# InterfacesA_FPGA.net
KiCad netlist of a schematic drawn in Altium Designer
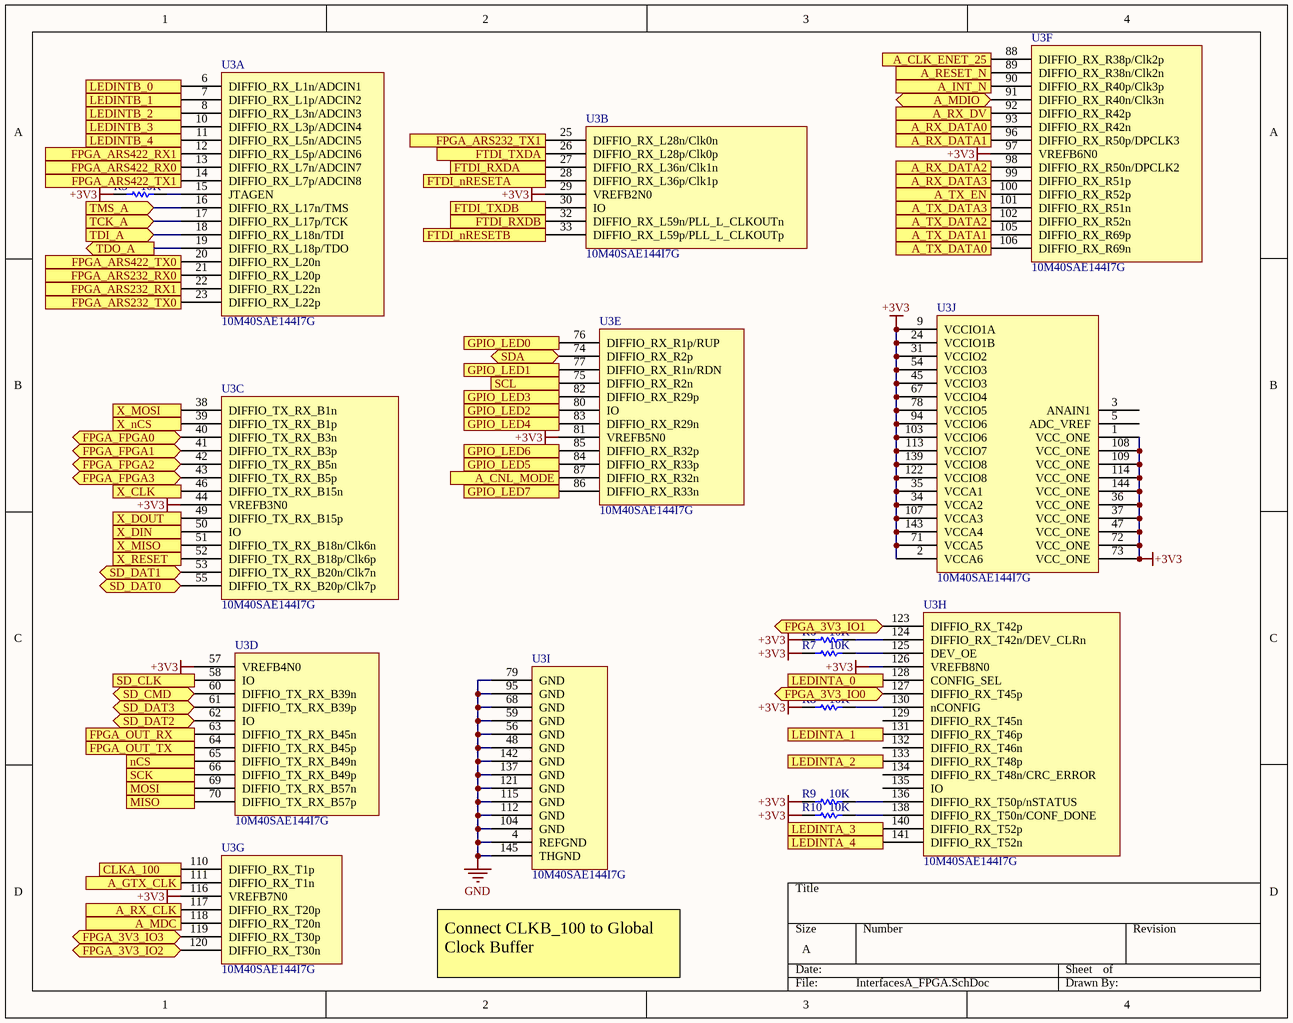
[diagram p0: InterfacesA_FPGA.SchDoc]

(export (version "E")
  (design (tool "Eeschema 10.0.6"))
  (components
    (comp (ref "R5")
      (value "10K")
      (footprint "RES_0805")
      (fields (field (name "Comment") "RES_0805"))
      (libsource (lib "AdapterLib") (part "RES_0805"))
    )
    (comp (ref "R6")
      (value "10K")
      (footprint "RES_0805")
      (fields (field (name "Comment") "RES_0805"))
      (libsource (lib "AdapterLib") (part "RES_0805"))
    )
    (comp (ref "R7")
      (value "10K")
      (footprint "RES_0805")
      (fields (field (name "Comment") "RES_0805"))
      (libsource (lib "AdapterLib") (part "RES_0805"))
    )
    (comp (ref "R8")
      (value "10K")
      (footprint "RES_0805")
      (fields (field (name "Comment") "RES_0805"))
      (libsource (lib "AdapterLib") (part "RES_0805"))
    )
    (comp (ref "R9")
      (value "10K")
      (footprint "RES_0805")
      (fields (field (name "Comment") "RES_0805"))
      (libsource (lib "AdapterLib") (part "RES_0805"))
    )
    (comp (ref "R10")
      (value "10K")
      (footprint "RES_0805")
      (fields (field (name "Comment") "RES_0805"))
      (libsource (lib "AdapterLib") (part "RES_0805"))
    )
    (comp (ref "U3")
      (value "10M40SAE144I7G")
      (footprint "10M40SAE144I7G")
      (description "IC FPGA 101 I/O 144EQFP")
      (libsource (lib "AdapterLib") (part "10M40SAE144I7G"))
    )
  )
  (nets
    (net (code "1") (name "+3V3") (class "Default")
      (node (ref "R10") (pin "2") (pinfunction "2_2") (pintype "passive"))
      (node (ref "R5") (pin "2") (pinfunction "2_2") (pintype "passive"))
      (node (ref "R6") (pin "2") (pinfunction "2_2") (pintype "passive"))
      (node (ref "R7") (pin "2") (pinfunction "2_2") (pintype "passive"))
      (node (ref "R8") (pin "2") (pinfunction "2_2") (pintype "passive"))
      (node (ref "R9") (pin "2") (pinfunction "2_2") (pintype "passive"))
      (node (ref "U3") (pin "1") (pinfunction "VCC_ONE_1") (pintype "passive"))
      (node (ref "U3") (pin "103") (pinfunction "VCCIO6_103") (pintype "passive"))
      (node (ref "U3") (pin "107") (pinfunction "VCCA3_107") (pintype "passive"))
      (node (ref "U3") (pin "108") (pinfunction "VCC_ONE_108") (pintype "passive"))
      (node (ref "U3") (pin "109") (pinfunction "VCC_ONE_109") (pintype "passive"))
      (node (ref "U3") (pin "113") (pinfunction "VCCIO7_113") (pintype "passive"))
      (node (ref "U3") (pin "114") (pinfunction "VCC_ONE_114") (pintype "passive"))
      (node (ref "U3") (pin "116") (pinfunction "VREFB7N0_116") (pintype "passive"))
      (node (ref "U3") (pin "122") (pinfunction "VCCIO8_122") (pintype "passive"))
      (node (ref "U3") (pin "126") (pinfunction "VREFB8N0_126") (pintype "passive"))
      (node (ref "U3") (pin "139") (pinfunction "VCCIO8_139") (pintype "passive"))
      (node (ref "U3") (pin "143") (pinfunction "VCCA4_143") (pintype "passive"))
      (node (ref "U3") (pin "144") (pinfunction "VCC_ONE_144") (pintype "passive"))
      (node (ref "U3") (pin "2") (pinfunction "VCCA6_2") (pintype "passive"))
      (node (ref "U3") (pin "24") (pinfunction "VCCIO1B_24") (pintype "passive"))
      (node (ref "U3") (pin "29") (pinfunction "VREFB2N0_29") (pintype "passive"))
      (node (ref "U3") (pin "31") (pinfunction "VCCIO2_31") (pintype "passive"))
      (node (ref "U3") (pin "34") (pinfunction "VCCA2_34") (pintype "passive"))
      (node (ref "U3") (pin "35") (pinfunction "VCCA1_35") (pintype "passive"))
      (node (ref "U3") (pin "36") (pinfunction "VCC_ONE_36") (pintype "passive"))
      (node (ref "U3") (pin "37") (pinfunction "VCC_ONE_37") (pintype "passive"))
      (node (ref "U3") (pin "44") (pinfunction "VREFB3N0_44") (pintype "passive"))
      (node (ref "U3") (pin "45") (pinfunction "VCCIO3_45") (pintype "passive"))
      (node (ref "U3") (pin "47") (pinfunction "VCC_ONE_47") (pintype "passive"))
      (node (ref "U3") (pin "54") (pinfunction "VCCIO3_54") (pintype "passive"))
      (node (ref "U3") (pin "57") (pinfunction "VREFB4N0_57") (pintype "passive"))
      (node (ref "U3") (pin "67") (pinfunction "VCCIO4_67") (pintype "passive"))
      (node (ref "U3") (pin "71") (pinfunction "VCCA5_71") (pintype "passive"))
      (node (ref "U3") (pin "72") (pinfunction "VCC_ONE_72") (pintype "passive"))
      (node (ref "U3") (pin "73") (pinfunction "VCC_ONE_73") (pintype "passive"))
      (node (ref "U3") (pin "78") (pinfunction "VCCIO5_78") (pintype "passive"))
      (node (ref "U3") (pin "81") (pinfunction "VREFB5N0_81") (pintype "passive"))
      (node (ref "U3") (pin "9") (pinfunction "VCCIO1A_9") (pintype "passive"))
      (node (ref "U3") (pin "94") (pinfunction "VCCIO6_94") (pintype "passive"))
      (node (ref "U3") (pin "97") (pinfunction "VREFB6N0_97") (pintype "passive"))
    )
    (net (code "2") (name "/A_CLK_ENET_25") (class "Default")
      (node (ref "U3") (pin "88") (pinfunction "DIFFIO_RX_R38p/Clk2p_88") (pintype "passive"))
    )
    (net (code "3") (name "/A_CNL_MODE") (class "Default")
      (node (ref "U3") (pin "87") (pinfunction "DIFFIO_RX_R32n_87") (pintype "passive"))
    )
    (net (code "4") (name "/A_GTX_CLK") (class "Default")
      (node (ref "U3") (pin "111") (pinfunction "DIFFIO_RX_T1n_111") (pintype "passive"))
    )
    (net (code "5") (name "/A_INT_N") (class "Default")
      (node (ref "U3") (pin "90") (pinfunction "DIFFIO_RX_R40p/Clk3p_90") (pintype "passive"))
    )
    (net (code "6") (name "/A_MDC") (class "Default")
      (node (ref "U3") (pin "118") (pinfunction "DIFFIO_RX_T20n_118") (pintype "passive"))
    )
    (net (code "7") (name "/A_MDIO") (class "Default")
      (node (ref "U3") (pin "91") (pinfunction "DIFFIO_RX_R40n/Clk3n_91") (pintype "passive"))
    )
    (net (code "8") (name "/A_RESET_N") (class "Default")
      (node (ref "U3") (pin "89") (pinfunction "DIFFIO_RX_R38n/Clk2n_89") (pintype "passive"))
    )
    (net (code "9") (name "/A_RX_CLK") (class "Default")
      (node (ref "U3") (pin "117") (pinfunction "DIFFIO_RX_T20p_117") (pintype "passive"))
    )
    (net (code "10") (name "/A_RX_DATA0") (class "Default")
      (node (ref "U3") (pin "93") (pinfunction "DIFFIO_RX_R42n_93") (pintype "passive"))
    )
    (net (code "11") (name "/A_RX_DATA1") (class "Default")
      (node (ref "U3") (pin "96") (pinfunction "DIFFIO_RX_R50p/DPCLK3_96") (pintype "passive"))
    )
    (net (code "12") (name "/A_RX_DATA2") (class "Default")
      (node (ref "U3") (pin "98") (pinfunction "DIFFIO_RX_R50n/DPCLK2_98") (pintype "passive"))
    )
    (net (code "13") (name "/A_RX_DATA3") (class "Default")
      (node (ref "U3") (pin "99") (pinfunction "DIFFIO_RX_R51p_99") (pintype "passive"))
    )
    (net (code "14") (name "/A_RX_DV") (class "Default")
      (node (ref "U3") (pin "92") (pinfunction "DIFFIO_RX_R42p_92") (pintype "passive"))
    )
    (net (code "15") (name "/A_TX_DATA0") (class "Default")
      (node (ref "U3") (pin "106") (pinfunction "DIFFIO_RX_R69n_106") (pintype "passive"))
    )
    (net (code "16") (name "/A_TX_DATA1") (class "Default")
      (node (ref "U3") (pin "105") (pinfunction "DIFFIO_RX_R69p_105") (pintype "passive"))
    )
    (net (code "17") (name "/A_TX_DATA2") (class "Default")
      (node (ref "U3") (pin "102") (pinfunction "DIFFIO_RX_R52n_102") (pintype "passive"))
    )
    (net (code "18") (name "/A_TX_DATA3") (class "Default")
      (node (ref "U3") (pin "101") (pinfunction "DIFFIO_RX_R51n_101") (pintype "passive"))
    )
    (net (code "19") (name "/A_TX_EN") (class "Default")
      (node (ref "U3") (pin "100") (pinfunction "DIFFIO_RX_R52p_100") (pintype "passive"))
    )
    (net (code "20") (name "/CLKA_100") (class "Default")
      (node (ref "U3") (pin "110") (pinfunction "DIFFIO_RX_T1p_110") (pintype "passive"))
    )
    (net (code "21") (name "/FPGA_3V3_IO0") (class "Default")
      (node (ref "U3") (pin "127") (pinfunction "DIFFIO_RX_T45p_127") (pintype "passive"))
    )
    (net (code "22") (name "/FPGA_3V3_IO1") (class "Default")
      (node (ref "U3") (pin "123") (pinfunction "DIFFIO_RX_T42p_123") (pintype "passive"))
    )
    (net (code "23") (name "/FPGA_3V3_IO2") (class "Default")
      (node (ref "U3") (pin "120") (pinfunction "DIFFIO_RX_T30n_120") (pintype "passive"))
    )
    (net (code "24") (name "/FPGA_3V3_IO3") (class "Default")
      (node (ref "U3") (pin "119") (pinfunction "DIFFIO_RX_T30p_119") (pintype "passive"))
    )
    (net (code "25") (name "/FPGA_ARS232_RX0") (class "Default")
      (node (ref "U3") (pin "21") (pinfunction "DIFFIO_RX_L20p_21") (pintype "passive"))
    )
    (net (code "26") (name "/FPGA_ARS232_RX1") (class "Default")
      (node (ref "U3") (pin "22") (pinfunction "DIFFIO_RX_L22n_22") (pintype "passive"))
    )
    (net (code "27") (name "/FPGA_ARS232_TX0") (class "Default")
      (node (ref "U3") (pin "23") (pinfunction "DIFFIO_RX_L22p_23") (pintype "passive"))
    )
    (net (code "28") (name "/FPGA_ARS232_TX1") (class "Default")
      (node (ref "U3") (pin "25") (pinfunction "DIFFIO_RX_L28n/Clk0n_25") (pintype "passive"))
    )
    (net (code "29") (name "/FPGA_ARS422_RX0") (class "Default")
      (node (ref "U3") (pin "13") (pinfunction "DIFFIO_RX_L7n/ADCIN7_13") (pintype "passive"))
    )
    (net (code "30") (name "/FPGA_ARS422_RX1") (class "Default")
      (node (ref "U3") (pin "12") (pinfunction "DIFFIO_RX_L5p/ADCIN6_12") (pintype "passive"))
    )
    (net (code "31") (name "/FPGA_ARS422_TX0") (class "Default")
      (node (ref "U3") (pin "20") (pinfunction "DIFFIO_RX_L20n_20") (pintype "passive"))
    )
    (net (code "32") (name "/FPGA_ARS422_TX1") (class "Default")
      (node (ref "U3") (pin "14") (pinfunction "DIFFIO_RX_L7p/ADCIN8_14") (pintype "passive"))
    )
    (net (code "33") (name "/FPGA_FPGA0") (class "Default")
      (node (ref "U3") (pin "40") (pinfunction "DIFFIO_TX_RX_B3n_40") (pintype "passive"))
    )
    (net (code "34") (name "/FPGA_FPGA1") (class "Default")
      (node (ref "U3") (pin "41") (pinfunction "DIFFIO_TX_RX_B3p_41") (pintype "passive"))
    )
    (net (code "35") (name "/FPGA_FPGA2") (class "Default")
      (node (ref "U3") (pin "42") (pinfunction "DIFFIO_TX_RX_B5n_42") (pintype "passive"))
    )
    (net (code "36") (name "/FPGA_FPGA3") (class "Default")
      (node (ref "U3") (pin "43") (pinfunction "DIFFIO_TX_RX_B5p_43") (pintype "passive"))
    )
    (net (code "37") (name "/FPGA_OUT_RX") (class "Default")
      (node (ref "U3") (pin "63") (pinfunction "DIFFIO_TX_RX_B45n_63") (pintype "passive"))
    )
    (net (code "38") (name "/FPGA_OUT_TX") (class "Default")
      (node (ref "U3") (pin "64") (pinfunction "DIFFIO_TX_RX_B45p_64") (pintype "passive"))
    )
    (net (code "39") (name "/FTDI_RXDA") (class "Default")
      (node (ref "U3") (pin "27") (pinfunction "DIFFIO_RX_L36n/Clk1n_27") (pintype "passive"))
    )
    (net (code "40") (name "/FTDI_RXDB") (class "Default")
      (node (ref "U3") (pin "32") (pinfunction "DIFFIO_RX_L59n/PLL_L_CLKOUTn_32") (pintype "passive"))
    )
    (net (code "41") (name "/FTDI_TXDA") (class "Default")
      (node (ref "U3") (pin "26") (pinfunction "DIFFIO_RX_L28p/Clk0p_26") (pintype "passive"))
    )
    (net (code "42") (name "/FTDI_TXDB") (class "Default")
      (node (ref "U3") (pin "30") (pinfunction "IO_30") (pintype "passive"))
    )
    (net (code "43") (name "/FTDI_nRESETA") (class "Default")
      (node (ref "U3") (pin "28") (pinfunction "DIFFIO_RX_L36p/Clk1p_28") (pintype "passive"))
    )
    (net (code "44") (name "/FTDI_nRESETB") (class "Default")
      (node (ref "U3") (pin "33") (pinfunction "DIFFIO_RX_L59p/PLL_L_CLKOUTp_33") (pintype "passive"))
    )
    (net (code "45") (name "/GPIO_LED0") (class "Default")
      (node (ref "U3") (pin "76") (pinfunction "DIFFIO_RX_R1p/RUP_76") (pintype "passive"))
    )
    (net (code "46") (name "/GPIO_LED1") (class "Default")
      (node (ref "U3") (pin "77") (pinfunction "DIFFIO_RX_R1n/RDN_77") (pintype "passive"))
    )
    (net (code "47") (name "/GPIO_LED2") (class "Default")
      (node (ref "U3") (pin "80") (pinfunction "IO_80") (pintype "passive"))
    )
    (net (code "48") (name "/GPIO_LED3") (class "Default")
      (node (ref "U3") (pin "82") (pinfunction "DIFFIO_RX_R29p_82") (pintype "passive"))
    )
    (net (code "49") (name "/GPIO_LED4") (class "Default")
      (node (ref "U3") (pin "83") (pinfunction "DIFFIO_RX_R29n_83") (pintype "passive"))
    )
    (net (code "50") (name "/GPIO_LED5") (class "Default")
      (node (ref "U3") (pin "84") (pinfunction "DIFFIO_RX_R33p_84") (pintype "passive"))
    )
    (net (code "51") (name "/GPIO_LED6") (class "Default")
      (node (ref "U3") (pin "85") (pinfunction "DIFFIO_RX_R32p_85") (pintype "passive"))
    )
    (net (code "52") (name "/GPIO_LED7") (class "Default")
      (node (ref "U3") (pin "86") (pinfunction "DIFFIO_RX_R33n_86") (pintype "passive"))
    )
    (net (code "53") (name "/LEDINTA_0") (class "Default")
      (node (ref "U3") (pin "128") (pinfunction "CONFIG_SEL_128") (pintype "passive"))
    )
    (net (code "54") (name "/LEDINTA_1") (class "Default")
      (node (ref "U3") (pin "131") (pinfunction "DIFFIO_RX_T46p_131") (pintype "passive"))
    )
    (net (code "55") (name "/LEDINTA_2") (class "Default")
      (node (ref "U3") (pin "133") (pinfunction "DIFFIO_RX_T48p_133") (pintype "passive"))
    )
    (net (code "56") (name "/LEDINTA_3") (class "Default")
      (node (ref "U3") (pin "140") (pinfunction "DIFFIO_RX_T52p_140") (pintype "passive"))
    )
    (net (code "57") (name "/LEDINTA_4") (class "Default")
      (node (ref "U3") (pin "141") (pinfunction "DIFFIO_RX_T52n_141") (pintype "passive"))
    )
    (net (code "58") (name "/LEDINTB_0") (class "Default")
      (node (ref "U3") (pin "6") (pinfunction "DIFFIO_RX_L1n/ADCIN1_6") (pintype "passive"))
    )
    (net (code "59") (name "/LEDINTB_1") (class "Default")
      (node (ref "U3") (pin "7") (pinfunction "DIFFIO_RX_L1p/ADCIN2_7") (pintype "passive"))
    )
    (net (code "60") (name "/LEDINTB_2") (class "Default")
      (node (ref "U3") (pin "8") (pinfunction "DIFFIO_RX_L3n/ADCIN3_8") (pintype "passive"))
    )
    (net (code "61") (name "/LEDINTB_3") (class "Default")
      (node (ref "U3") (pin "10") (pinfunction "DIFFIO_RX_L3p/ADCIN4_10") (pintype "passive"))
    )
    (net (code "62") (name "/LEDINTB_4") (class "Default")
      (node (ref "U3") (pin "11") (pinfunction "DIFFIO_RX_L5n/ADCIN5_11") (pintype "passive"))
    )
    (net (code "63") (name "/MISO") (class "Default")
      (node (ref "U3") (pin "70") (pinfunction "DIFFIO_TX_RX_B57p_70") (pintype "passive"))
    )
    (net (code "64") (name "/MOSI") (class "Default")
      (node (ref "U3") (pin "69") (pinfunction "DIFFIO_TX_RX_B57n_69") (pintype "passive"))
    )
    (net (code "65") (name "/SCK") (class "Default")
      (node (ref "U3") (pin "66") (pinfunction "DIFFIO_TX_RX_B49p_66") (pintype "passive"))
    )
    (net (code "66") (name "/SCL") (class "Default")
      (node (ref "U3") (pin "75") (pinfunction "DIFFIO_RX_R2n_75") (pintype "passive"))
    )
    (net (code "67") (name "/SDA") (class "Default")
      (node (ref "U3") (pin "74") (pinfunction "DIFFIO_RX_R2p_74") (pintype "passive"))
    )
    (net (code "68") (name "/SD_CLK") (class "Default")
      (node (ref "U3") (pin "58") (pinfunction "IO_58") (pintype "passive"))
    )
    (net (code "69") (name "/SD_CMD") (class "Default")
      (node (ref "U3") (pin "60") (pinfunction "DIFFIO_TX_RX_B39n_60") (pintype "passive"))
    )
    (net (code "70") (name "/SD_DAT0") (class "Default")
      (node (ref "U3") (pin "55") (pinfunction "DIFFIO_TX_RX_B20p/Clk7p_55") (pintype "passive"))
    )
    (net (code "71") (name "/SD_DAT1") (class "Default")
      (node (ref "U3") (pin "53") (pinfunction "DIFFIO_TX_RX_B20n/Clk7n_53") (pintype "passive"))
    )
    (net (code "72") (name "/SD_DAT2") (class "Default")
      (node (ref "U3") (pin "62") (pinfunction "IO_62") (pintype "passive"))
    )
    (net (code "73") (name "/SD_DAT3") (class "Default")
      (node (ref "U3") (pin "61") (pinfunction "DIFFIO_TX_RX_B39p_61") (pintype "passive"))
    )
    (net (code "74") (name "/TCK_A") (class "Default")
      (node (ref "U3") (pin "17") (pinfunction "DIFFIO_RX_L17p/TCK_17") (pintype "passive"))
    )
    (net (code "75") (name "/TDI_A") (class "Default")
      (node (ref "U3") (pin "18") (pinfunction "DIFFIO_RX_L18n/TDI_18") (pintype "passive"))
    )
    (net (code "76") (name "/TDO_A") (class "Default")
      (node (ref "U3") (pin "19") (pinfunction "DIFFIO_RX_L18p/TDO_19") (pintype "passive"))
    )
    (net (code "77") (name "/TMS_A") (class "Default")
      (node (ref "U3") (pin "16") (pinfunction "DIFFIO_RX_L17n/TMS_16") (pintype "passive"))
    )
    (net (code "78") (name "/X_CLK") (class "Default")
      (node (ref "U3") (pin "46") (pinfunction "DIFFIO_TX_RX_B15n_46") (pintype "passive"))
    )
    (net (code "79") (name "/X_DIN") (class "Default")
      (node (ref "U3") (pin "50") (pinfunction "IO_50") (pintype "passive"))
    )
    (net (code "80") (name "/X_DOUT") (class "Default")
      (node (ref "U3") (pin "49") (pinfunction "DIFFIO_TX_RX_B15p_49") (pintype "passive"))
    )
    (net (code "81") (name "/X_MISO") (class "Default")
      (node (ref "U3") (pin "51") (pinfunction "DIFFIO_TX_RX_B18n/Clk6n_51") (pintype "passive"))
    )
    (net (code "82") (name "/X_MOSI") (class "Default")
      (node (ref "U3") (pin "38") (pinfunction "DIFFIO_TX_RX_B1n_38") (pintype "passive"))
    )
    (net (code "83") (name "/X_RESET") (class "Default")
      (node (ref "U3") (pin "52") (pinfunction "DIFFIO_TX_RX_B18p/Clk6p_52") (pintype "passive"))
    )
    (net (code "84") (name "/X_nCS") (class "Default")
      (node (ref "U3") (pin "39") (pinfunction "DIFFIO_TX_RX_B1p_39") (pintype "passive"))
    )
    (net (code "85") (name "/nCS") (class "Default")
      (node (ref "U3") (pin "65") (pinfunction "DIFFIO_TX_RX_B49n_65") (pintype "passive"))
    )
    (net (code "86") (name "GND") (class "Default")
      (node (ref "U3") (pin "104") (pinfunction "GND_104") (pintype "passive"))
      (node (ref "U3") (pin "112") (pinfunction "GND_112") (pintype "passive"))
      (node (ref "U3") (pin "115") (pinfunction "GND_115") (pintype "passive"))
      (node (ref "U3") (pin "121") (pinfunction "GND_121") (pintype "passive"))
      (node (ref "U3") (pin "137") (pinfunction "GND_137") (pintype "passive"))
      (node (ref "U3") (pin "142") (pinfunction "GND_142") (pintype "passive"))
      (node (ref "U3") (pin "145") (pinfunction "THGND_145") (pintype "passive"))
      (node (ref "U3") (pin "4") (pinfunction "REFGND_4") (pintype "passive"))
      (node (ref "U3") (pin "48") (pinfunction "GND_48") (pintype "passive"))
      (node (ref "U3") (pin "56") (pinfunction "GND_56") (pintype "passive"))
      (node (ref "U3") (pin "59") (pinfunction "GND_59") (pintype "passive"))
      (node (ref "U3") (pin "68") (pinfunction "GND_68") (pintype "passive"))
      (node (ref "U3") (pin "79") (pinfunction "GND_79") (pintype "passive"))
      (node (ref "U3") (pin "95") (pinfunction "GND_95") (pintype "passive"))
    )
    (net (code "87") (name "Net-(U3A-JTAGEN)") (class "Default")
      (node (ref "R5") (pin "1") (pinfunction "1_1") (pintype "passive"))
      (node (ref "U3") (pin "15") (pinfunction "JTAGEN_15") (pintype "passive"))
    )
    (net (code "88") (name "Net-(U3H-DEV_OE)") (class "Default")
      (node (ref "R7") (pin "1") (pinfunction "1_1") (pintype "passive"))
      (node (ref "U3") (pin "125") (pinfunction "DEV_OE_125") (pintype "passive"))
    )
    (net (code "89") (name "Net-(U3H-DIFFIO_RX_T42n{slash}DEV_CLRn)") (class "Default")
      (node (ref "R6") (pin "1") (pinfunction "1_1") (pintype "passive"))
      (node (ref "U3") (pin "124") (pinfunction "DIFFIO_RX_T42n/DEV_CLRn_124") (pintype "passive"))
    )
    (net (code "90") (name "Net-(U3H-DIFFIO_RX_T50n{slash}CONF_DONE)") (class "Default")
      (node (ref "R10") (pin "1") (pinfunction "1_1") (pintype "passive"))
      (node (ref "U3") (pin "138") (pinfunction "DIFFIO_RX_T50n/CONF_DONE_138") (pintype "passive"))
    )
    (net (code "91") (name "Net-(U3H-DIFFIO_RX_T50p{slash}nSTATUS)") (class "Default")
      (node (ref "R9") (pin "1") (pinfunction "1_1") (pintype "passive"))
      (node (ref "U3") (pin "136") (pinfunction "DIFFIO_RX_T50p/nSTATUS_136") (pintype "passive"))
    )
    (net (code "92") (name "Net-(U3H-nCONFIG)") (class "Default")
      (node (ref "R8") (pin "1") (pinfunction "1_1") (pintype "passive"))
      (node (ref "U3") (pin "130") (pinfunction "nCONFIG_130") (pintype "passive"))
    )
    (net (code "93") (name "unconnected-(U3H-DIFFIO_RX_T45n-Pad129)") (class "Default")
      (node (ref "U3") (pin "129") (pinfunction "DIFFIO_RX_T45n_129") (pintype "passive"))
    )
    (net (code "94") (name "unconnected-(U3H-DIFFIO_RX_T46n-Pad132)") (class "Default")
      (node (ref "U3") (pin "132") (pinfunction "DIFFIO_RX_T46n_132") (pintype "passive"))
    )
    (net (code "95") (name "unconnected-(U3H-DIFFIO_RX_T48n{slash}CRC_ERROR-Pad134)") (class "Default")
      (node (ref "U3") (pin "134") (pinfunction "DIFFIO_RX_T48n/CRC_ERROR_134") (pintype "passive"))
    )
    (net (code "96") (name "unconnected-(U3H-IO-Pad135)") (class "Default")
      (node (ref "U3") (pin "135") (pinfunction "IO_135") (pintype "passive"))
    )
    (net (code "97") (name "unconnected-(U3J-ADC_VREF-Pad5)") (class "Default")
      (node (ref "U3") (pin "5") (pinfunction "ADC_VREF_5") (pintype "passive"))
    )
    (net (code "98") (name "unconnected-(U3J-ANAIN1-Pad3)") (class "Default")
      (node (ref "U3") (pin "3") (pinfunction "ANAIN1_3") (pintype "passive"))
    )
  )
)
